# OTA_VCA_Test.net
KiCad netlist of a schematic drawn in EAGLE
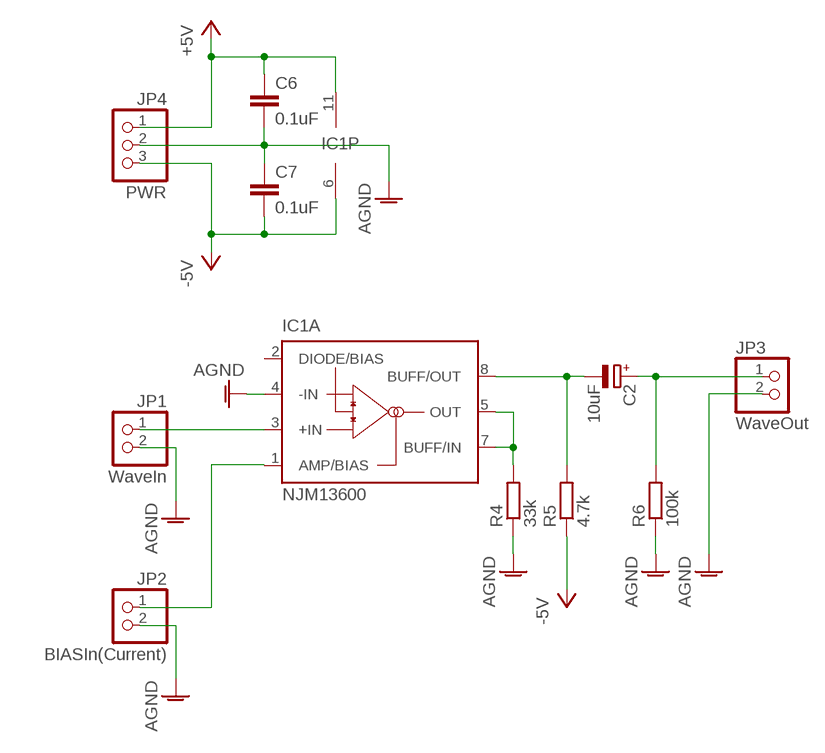
[diagram p0: schematic, sheet 1]

(export (version "E")
  (design (tool "Eeschema 10.0.6"))
  (components
    (comp (ref "C2")
      (value "10uF")
      (footprint "eagle-import:E2,5-7")
      (libsource (lib "eagle-import") (part "CPOL-EUE2.5-7"))
    )
    (comp (ref "C6")
      (value "0.1uF")
      (footprint "eagle-import:C025-024X044")
      (libsource (lib "eagle-import") (part "C-EU025-024X044"))
    )
    (comp (ref "C7")
      (value "0.1uF")
      (footprint "eagle-import:C025-024X044")
      (libsource (lib "eagle-import") (part "C-EU025-024X044"))
    )
    (comp (ref "IC1")
      (value "NJM13600")
      (footprint "eagle-import:DIL16")
      (libsource (lib "eagle-import") (part "LM13600N"))
    )
    (comp (ref "JP1")
      (value "WaveIn")
      (footprint "eagle-import:1X02")
      (libsource (lib "eagle-import") (part "PINHD-1X2"))
    )
    (comp (ref "JP2")
      (value "BIASIn(Current)")
      (footprint "eagle-import:1X02")
      (libsource (lib "eagle-import") (part "PINHD-1X2"))
    )
    (comp (ref "JP3")
      (value "WaveOut")
      (footprint "eagle-import:1X02")
      (libsource (lib "eagle-import") (part "PINHD-1X2"))
    )
    (comp (ref "JP4")
      (value "PWR")
      (footprint "eagle-import:1X03")
      (libsource (lib "eagle-import") (part "PINHD-1X3"))
    )
    (comp (ref "R4")
      (value "33k")
      (footprint "eagle-import:0207_7")
      (libsource (lib "eagle-import") (part "R-EU_0207/7"))
    )
    (comp (ref "R5")
      (value "4.7k")
      (footprint "eagle-import:0207_7")
      (libsource (lib "eagle-import") (part "R-EU_0207/7"))
    )
    (comp (ref "R6")
      (value "100k")
      (footprint "eagle-import:0207_7")
      (libsource (lib "eagle-import") (part "R-EU_0207/7"))
    )
  )
  (nets
    (net (code "1") (name "+5V") (class "Default")
      (node (ref "C6") (pin "1") (pinfunction "1_1") (pintype "passive"))
      (node (ref "IC1") (pin "11") (pinfunction "V+_11") (pintype "power_in"))
      (node (ref "JP4") (pin "1") (pinfunction "1_1") (pintype "passive"))
    )
    (net (code "2") (name "-5V") (class "Default")
      (node (ref "C7") (pin "2") (pinfunction "2_2") (pintype "passive"))
      (node (ref "IC1") (pin "6") (pinfunction "V-_6") (pintype "power_in"))
      (node (ref "JP4") (pin "3") (pinfunction "3_3") (pintype "passive"))
      (node (ref "R5") (pin "1") (pinfunction "1_1") (pintype "passive"))
    )
    (net (code "3") (name "AGND") (class "Default")
      (node (ref "C6") (pin "2") (pinfunction "2_2") (pintype "passive"))
      (node (ref "C7") (pin "1") (pinfunction "1_1") (pintype "passive"))
      (node (ref "IC1") (pin "4") (pinfunction "-IN_4") (pintype "input"))
      (node (ref "JP1") (pin "2") (pinfunction "2_2") (pintype "passive"))
      (node (ref "JP2") (pin "2") (pinfunction "2_2") (pintype "passive"))
      (node (ref "JP3") (pin "2") (pinfunction "2_2") (pintype "passive"))
      (node (ref "JP4") (pin "2") (pinfunction "2_2") (pintype "passive"))
      (node (ref "R4") (pin "1") (pinfunction "1_1") (pintype "passive"))
      (node (ref "R6") (pin "1") (pinfunction "1_1") (pintype "passive"))
    )
    (net (code "4") (name "Net-(C2-Pad+)") (class "Default")
      (node (ref "C2") (pin "+") (pinfunction "+_+") (pintype "passive"))
      (node (ref "JP3") (pin "1") (pinfunction "1_1") (pintype "passive"))
      (node (ref "R6") (pin "2") (pinfunction "2_2") (pintype "passive"))
    )
    (net (code "5") (name "Net-(IC1A-+IN)") (class "Default")
      (node (ref "IC1") (pin "3") (pinfunction "+IN_3") (pintype "input"))
      (node (ref "JP1") (pin "1") (pinfunction "1_1") (pintype "passive"))
    )
    (net (code "6") (name "Net-(IC1A-AMP{slash}BIAS)") (class "Default")
      (node (ref "IC1") (pin "1") (pinfunction "AMP/BIAS_1") (pintype "passive"))
      (node (ref "JP2") (pin "1") (pinfunction "1_1") (pintype "passive"))
    )
    (net (code "7") (name "Net-(IC1A-BUFF{slash}IN)") (class "Default")
      (node (ref "IC1") (pin "5") (pinfunction "OUT_5") (pintype "output"))
      (node (ref "IC1") (pin "7") (pinfunction "BUFF/IN_7") (pintype "input"))
      (node (ref "R4") (pin "2") (pinfunction "2_2") (pintype "passive"))
    )
    (net (code "8") (name "Net-(IC1A-BUFF{slash}OUT)") (class "Default")
      (node (ref "C2") (pin "-") (pinfunction "-_-") (pintype "passive"))
      (node (ref "IC1") (pin "8") (pinfunction "BUFF/OUT_8") (pintype "output"))
      (node (ref "R5") (pin "2") (pinfunction "2_2") (pintype "passive"))
    )
    (net (code "9") (name "unconnected-(IC1A-DIODE{slash}BIAS-Pad2)") (class "Default")
      (node (ref "IC1") (pin "2") (pinfunction "DIODE/BIAS_2") (pintype "passive"))
    )
  )
)
